# RX_Sheet1.net
KiCad netlist of a schematic drawn in Altium Designer
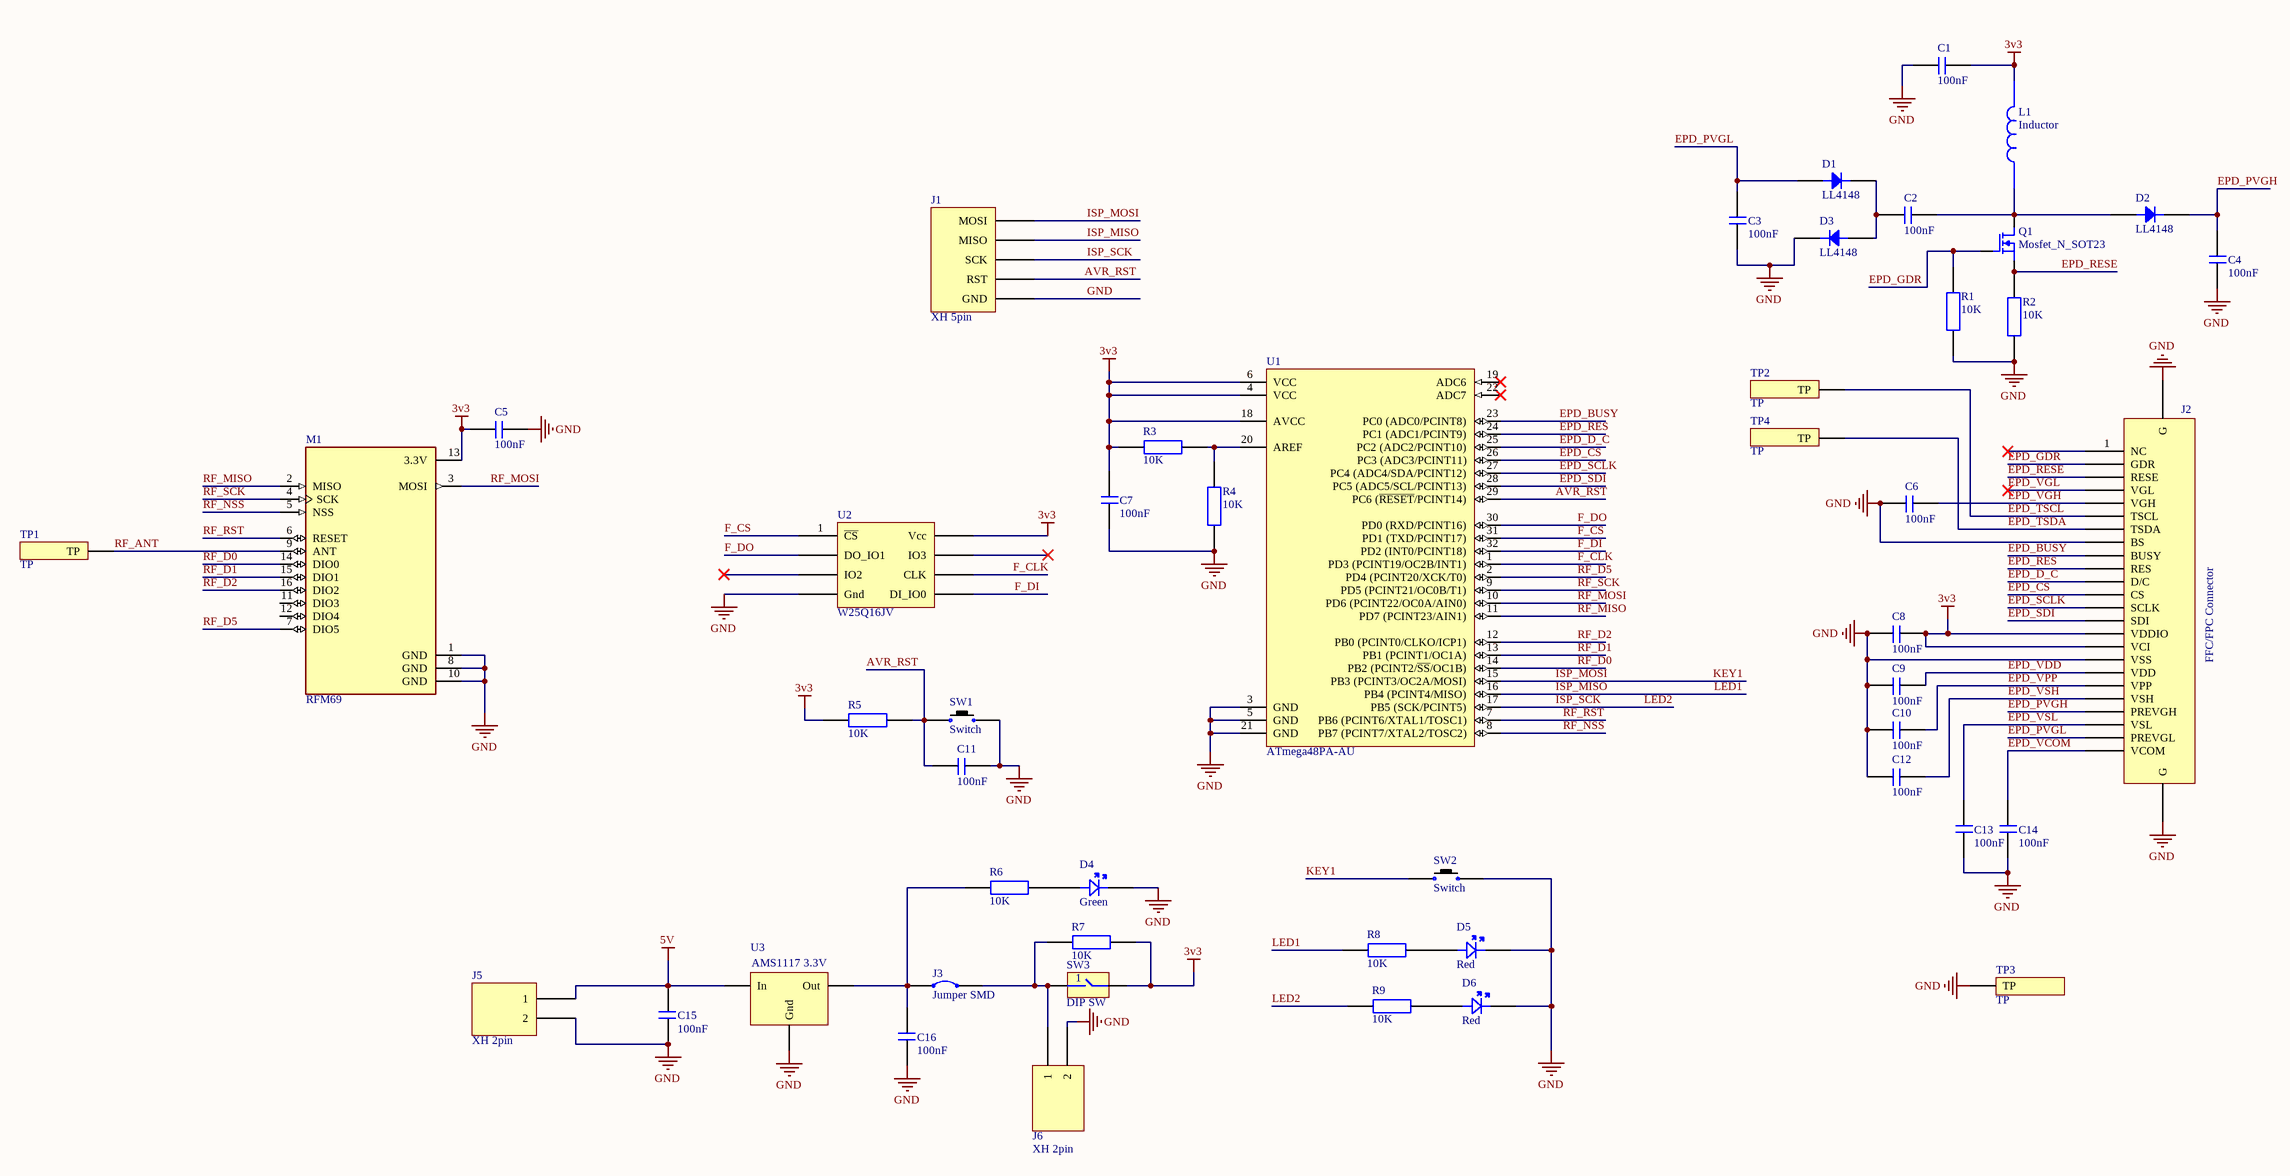
[diagram p0: RX_Sheet1.SchDoc]

(export (version "E")
  (design (tool "Eeschema 10.0.6"))
  (components
    (comp (ref "C1")
      (value "100nF")
      (footprint "CAP_0805")
      (description "Capacitor SMD 0805")
      (libsource (lib "My_Integrated_Library") (part "Cap0805"))
    )
    (comp (ref "C2")
      (value "100nF")
      (footprint "CAP_0805")
      (description "Capacitor SMD 0805")
      (libsource (lib "My_Integrated_Library") (part "Cap0805"))
    )
    (comp (ref "C3")
      (value "100nF")
      (footprint "CAP_0805")
      (description "Capacitor SMD 0805")
      (libsource (lib "My_Integrated_Library") (part "Cap0805"))
    )
    (comp (ref "C4")
      (value "100nF")
      (footprint "CAP_0805")
      (description "Capacitor SMD 0805")
      (libsource (lib "My_Integrated_Library") (part "Cap0805"))
    )
    (comp (ref "C5")
      (value "100nF")
      (footprint "CAP_0805")
      (description "Capacitor SMD 0805")
      (libsource (lib "My_Integrated_Library") (part "Cap0805"))
    )
    (comp (ref "C6")
      (value "100nF")
      (footprint "CAP_0805")
      (description "Capacitor SMD 0805")
      (libsource (lib "My_Integrated_Library") (part "Cap0805"))
    )
    (comp (ref "C7")
      (value "100nF")
      (footprint "CAP_0805")
      (description "Capacitor SMD 0805")
      (libsource (lib "My_Integrated_Library") (part "Cap0805"))
    )
    (comp (ref "C8")
      (value "100nF")
      (footprint "CAP_0805")
      (description "Capacitor SMD 0805")
      (libsource (lib "My_Integrated_Library") (part "Cap0805"))
    )
    (comp (ref "C9")
      (value "100nF")
      (footprint "CAP_0805")
      (description "Capacitor SMD 0805")
      (libsource (lib "My_Integrated_Library") (part "Cap0805"))
    )
    (comp (ref "C10")
      (value "100nF")
      (footprint "CAP_0805")
      (description "Capacitor SMD 0805")
      (libsource (lib "My_Integrated_Library") (part "Cap0805"))
    )
    (comp (ref "C11")
      (value "100nF")
      (footprint "CAP_0805")
      (description "Capacitor SMD 0805")
      (libsource (lib "My_Integrated_Library") (part "Cap0805"))
    )
    (comp (ref "C12")
      (value "100nF")
      (footprint "CAP_0805")
      (description "Capacitor SMD 0805")
      (libsource (lib "My_Integrated_Library") (part "Cap0805"))
    )
    (comp (ref "C13")
      (value "100nF")
      (footprint "CAP_0805")
      (description "Capacitor SMD 0805")
      (libsource (lib "My_Integrated_Library") (part "Cap0805"))
    )
    (comp (ref "C14")
      (value "100nF")
      (footprint "CAP_0805")
      (description "Capacitor SMD 0805")
      (libsource (lib "My_Integrated_Library") (part "Cap0805"))
    )
    (comp (ref "C15")
      (value "100nF")
      (footprint "CAP_0805")
      (description "Capacitor SMD 0805")
      (libsource (lib "My_Integrated_Library") (part "Cap0805"))
    )
    (comp (ref "C16")
      (value "100nF")
      (footprint "CAP_0805")
      (description "Capacitor SMD 0805")
      (libsource (lib "My_Integrated_Library") (part "Cap0805"))
    )
    (comp (ref "D1")
      (value "LL4148")
      (footprint "LL4148")
      (description "Diode SMD LL4148 1206")
      (libsource (lib "My_Integrated_Library") (part "Diode_LL4148"))
    )
    (comp (ref "D2")
      (value "LL4148")
      (footprint "LL4148")
      (description "Diode SMD LL4148 1206")
      (libsource (lib "My_Integrated_Library") (part "Diode_LL4148"))
    )
    (comp (ref "D3")
      (value "LL4148")
      (footprint "LL4148")
      (description "Diode SMD LL4148 1206")
      (libsource (lib "My_Integrated_Library") (part "Diode_LL4148"))
    )
    (comp (ref "D4")
      (value "Green")
      (footprint "LED_0805_Green")
      (description "LED SMD 0805 Green")
      (libsource (lib "My_Integrated_Library") (part "LED_0805_Green"))
    )
    (comp (ref "D5")
      (value "Red")
      (footprint "LED_0805_Red")
      (description "LED SMD 0805 Red")
      (libsource (lib "My_Integrated_Library") (part "LED_0805_Red"))
    )
    (comp (ref "D6")
      (value "Red")
      (footprint "LED_0805_Red")
      (description "LED SMD 0805 Red")
      (libsource (lib "My_Integrated_Library") (part "LED_0805_Red"))
    )
    (comp (ref "J1")
      (value "XH 5pin")
      (footprint "XH-5pin")
      (description "Connector XH Female 5-pin")
      (libsource (lib "My_Integrated_Library") (part "Con_XH_5pin"))
    )
    (comp (ref "J2")
      (value "FFC/FPC Connector")
      (footprint "EPD_CON_24")
      (libsource (lib "My_Integrated_Library") (part "EPD_con_24pin"))
    )
    (comp (ref "J3")
      (value "Jumper SMD")
      (footprint "Jumper_smd")
      (libsource (lib "My_Integrated_Library") (part "Jump_smd"))
    )
    (comp (ref "J5")
      (value "XH 2pin")
      (footprint "XH-2pin")
      (description "Connector XH Female 2-pin")
      (libsource (lib "My_Integrated_Library") (part "Con_XH_2pin"))
    )
    (comp (ref "J6")
      (value "XH 2pin")
      (footprint "XH-2pin")
      (description "Connector XH Female 2-pin")
      (libsource (lib "") (part "Con_XH_2pin_1"))
    )
    (comp (ref "L1")
      (value "Inductor")
      (footprint "L_5x5")
      (description "SMD Power Inductor 10X10mm")
      (libsource (lib "My_Integrated_Library") (part "Inductor_5x5"))
    )
    (comp (ref "M1")
      (value "RFM69")
      (footprint "RFM95W")
      (description "General ISM < 1GHz LoRaâ„¢ Transceiver Module 915MHz Surface Mount")
      (fields (field (name "MP") "RFM95W-915S2") (field (name "MF") "RF Solutions"))
      (libsource (lib "My_Integrated_Library") (part "RFM95W-915S2"))
    )
    (comp (ref "Q1")
      (value "Mosfet_N_SOT23")
      (footprint "SOT23 - N-Channel - duplicate")
      (description "MOSFET N-Channel SMD SOT23")
      (libsource (lib "My_Integrated_Library") (part "Mosfet_N_SOT23"))
    )
    (comp (ref "R1")
      (value "10K")
      (footprint "RES_0805")
      (description "Resistor SMD 0805")
      (libsource (lib "My_Integrated_Library") (part "Res0805"))
    )
    (comp (ref "R2")
      (value "10K")
      (footprint "RES_0805")
      (description "Resistor SMD 0805")
      (libsource (lib "My_Integrated_Library") (part "Res0805"))
    )
    (comp (ref "R3")
      (value "10K")
      (footprint "RES_0805")
      (description "Resistor SMD 0805")
      (libsource (lib "My_Integrated_Library") (part "Res0805"))
    )
    (comp (ref "R4")
      (value "10K")
      (footprint "RES_0805")
      (description "Resistor SMD 0805")
      (libsource (lib "My_Integrated_Library") (part "Res0805"))
    )
    (comp (ref "R5")
      (value "10K")
      (footprint "RES_0805")
      (description "Resistor SMD 0805")
      (libsource (lib "My_Integrated_Library") (part "Res0805"))
    )
    (comp (ref "R6")
      (value "10K")
      (footprint "RES_0805")
      (description "Resistor SMD 0805")
      (libsource (lib "My_Integrated_Library") (part "Res0805"))
    )
    (comp (ref "R7")
      (value "10K")
      (footprint "RES_0805")
      (description "Resistor SMD 0805")
      (libsource (lib "My_Integrated_Library") (part "Res0805"))
    )
    (comp (ref "R8")
      (value "10K")
      (footprint "RES_0805")
      (description "Resistor SMD 0805")
      (libsource (lib "My_Integrated_Library") (part "Res0805"))
    )
    (comp (ref "R9")
      (value "10K")
      (footprint "RES_0805")
      (description "Resistor SMD 0805")
      (libsource (lib "My_Integrated_Library") (part "Res0805"))
    )
    (comp (ref "SW1")
      (value "Switch")
      (footprint "Tact_SW_SMD")
      (description "Tact switch SMD 2pin")
      (libsource (lib "My_Integrated_Library") (part "Tact_sw"))
    )
    (comp (ref "SW2")
      (value "Switch")
      (footprint "Tact_SW_SMD")
      (description "Tact switch SMD 2pin")
      (libsource (lib "My_Integrated_Library") (part "Tact_sw"))
    )
    (comp (ref "SW3")
      (value "DIP SW")
      (footprint "DIP_SW_1key")
      (description "DIP Swtich 1 key")
      (libsource (lib "My_Integrated_Library") (part "DIP_SW_1"))
    )
    (comp (ref "TP1")
      (value "TP")
      (footprint "TP")
      (description "Test point")
      (libsource (lib "") (part "TP_1"))
    )
    (comp (ref "TP2")
      (value "TP")
      (footprint "TP")
      (description "Test point")
      (libsource (lib "") (part "TP_1"))
    )
    (comp (ref "TP3")
      (value "TP")
      (footprint "TP")
      (description "Test point")
      (libsource (lib "My_Integrated_Library") (part "TP"))
    )
    (comp (ref "TP4")
      (value "TP")
      (footprint "TP")
      (description "Test point")
      (libsource (lib "") (part "TP_1"))
    )
    (comp (ref "U1")
      (value "ATmega48PA-AU")
      (footprint "32A_M")
      (fields (field (name "PUBLISHER") "Altium Limited"))
      (libsource (lib "My_Integrated_Library") (part "ATmega48PA-AU"))
    )
    (comp (ref "U2")
      (value "W25Q16JV")
      (footprint "W25Q64")
      (description "Serial Flash Memory 64Mbit")
      (libsource (lib "My_Integrated_Library") (part "W25Q64JV"))
    )
    (comp (ref "U3")
      (value "AMS1117 3.3V")
      (footprint "AMS1117-SOT223")
      (description "AMS1117 Regulator 3.3V SMD SOT223")
      (libsource (lib "My_Integrated_Library") (part "AMS1117-SOT223"))
    )
  )
  (nets
    (net (code "1") (name "/AVR_RST") (class "Default")
      (node (ref "C11") (pin "1") (pinfunction "1_1") (pintype "passive"))
      (node (ref "J1") (pin "4") (pinfunction "RST_4") (pintype "passive"))
      (node (ref "R5") (pin "2") (pinfunction "2_2") (pintype "passive"))
      (node (ref "SW1") (pin "2") (pinfunction "2_2") (pintype "passive"))
      (node (ref "U1") (pin "29") (pinfunction "PC6_(~{RESET}/PCINT14)_29") (pintype "bidirectional"))
    )
    (net (code "2") (name "/EPD_BUSY") (class "Default")
      (node (ref "J2") (pin "9") (pinfunction "BUSY_9") (pintype "passive"))
      (node (ref "U1") (pin "23") (pinfunction "PC0_(ADC0/PCINT8)_23") (pintype "bidirectional"))
    )
    (net (code "3") (name "/EPD_CS") (class "Default")
      (node (ref "J2") (pin "12") (pinfunction "CS_12") (pintype "passive"))
      (node (ref "U1") (pin "26") (pinfunction "PC3_(ADC3/PCINT11)_26") (pintype "bidirectional"))
    )
    (net (code "4") (name "/EPD_D_C") (class "Default")
      (node (ref "J2") (pin "11") (pinfunction "D/C_11") (pintype "passive"))
      (node (ref "U1") (pin "25") (pinfunction "PC2_(ADC2/PCINT10)_25") (pintype "bidirectional"))
    )
    (net (code "5") (name "/EPD_GDR") (class "Default")
      (node (ref "J2") (pin "2") (pinfunction "GDR_2") (pintype "passive"))
      (node (ref "Q1") (pin "G") (pinfunction "G_G") (pintype "passive"))
      (node (ref "R1") (pin "2") (pinfunction "2_2") (pintype "passive"))
    )
    (net (code "6") (name "/EPD_PVGH") (class "Default")
      (node (ref "C4") (pin "2") (pinfunction "2_2") (pintype "passive"))
      (node (ref "D2") (pin "K") (pinfunction "K_K") (pintype "passive"))
      (node (ref "J2") (pin "21") (pinfunction "PREVGH_21") (pintype "passive"))
    )
    (net (code "7") (name "/EPD_PVGL") (class "Default")
      (node (ref "C3") (pin "2") (pinfunction "2_2") (pintype "passive"))
      (node (ref "D1") (pin "A") (pinfunction "A_A") (pintype "passive"))
      (node (ref "J2") (pin "23") (pinfunction "PREVGL_23") (pintype "passive"))
    )
    (net (code "8") (name "/EPD_RES") (class "Default")
      (node (ref "J2") (pin "10") (pinfunction "RES_10") (pintype "passive"))
      (node (ref "U1") (pin "24") (pinfunction "PC1_(ADC1/PCINT9)_24") (pintype "bidirectional"))
    )
    (net (code "9") (name "/EPD_RESE") (class "Default")
      (node (ref "J2") (pin "3") (pinfunction "RESE_3") (pintype "passive"))
      (node (ref "Q1") (pin "S") (pinfunction "S_S") (pintype "passive"))
      (node (ref "R2") (pin "2") (pinfunction "2_2") (pintype "passive"))
    )
    (net (code "10") (name "/EPD_SCLK") (class "Default")
      (node (ref "J2") (pin "13") (pinfunction "SCLK_13") (pintype "passive"))
      (node (ref "U1") (pin "27") (pinfunction "PC4_(ADC4/SDA/PCINT12)_27") (pintype "bidirectional"))
    )
    (net (code "11") (name "/EPD_SDI") (class "Default")
      (node (ref "J2") (pin "14") (pinfunction "SDI_14") (pintype "passive"))
      (node (ref "U1") (pin "28") (pinfunction "PC5_(ADC5/SCL/PCINT13)_28") (pintype "bidirectional"))
    )
    (net (code "12") (name "/EPD_TSCL") (class "Default")
      (node (ref "J2") (pin "6") (pinfunction "TSCL_6") (pintype "passive"))
      (node (ref "TP2") (pin "1") (pinfunction "TP_1") (pintype "passive"))
    )
    (net (code "13") (name "/EPD_TSDA") (class "Default")
      (node (ref "J2") (pin "7") (pinfunction "TSDA_7") (pintype "passive"))
      (node (ref "TP4") (pin "1") (pinfunction "TP_1") (pintype "passive"))
    )
    (net (code "14") (name "/EPD_VCOM") (class "Default")
      (node (ref "C14") (pin "2") (pinfunction "2_2") (pintype "passive"))
      (node (ref "J2") (pin "24") (pinfunction "VCOM_24") (pintype "passive"))
    )
    (net (code "15") (name "/EPD_VDD") (class "Default")
      (node (ref "C9") (pin "2") (pinfunction "2_2") (pintype "passive"))
      (node (ref "J2") (pin "18") (pinfunction "VDD_18") (pintype "passive"))
    )
    (net (code "16") (name "/EPD_VGH") (class "Default")
      (node (ref "C6") (pin "2") (pinfunction "2_2") (pintype "passive"))
      (node (ref "J2") (pin "5") (pinfunction "VGH_5") (pintype "passive"))
    )
    (net (code "17") (name "/EPD_VGL") (class "Default")
      (node (ref "J2") (pin "4") (pinfunction "VGL_4") (pintype "passive+no_connect"))
    )
    (net (code "18") (name "/EPD_VPP") (class "Default")
      (node (ref "C10") (pin "2") (pinfunction "2_2") (pintype "passive"))
      (node (ref "J2") (pin "19") (pinfunction "VPP_19") (pintype "passive"))
    )
    (net (code "19") (name "/EPD_VSH") (class "Default")
      (node (ref "C12") (pin "2") (pinfunction "2_2") (pintype "passive"))
      (node (ref "J2") (pin "20") (pinfunction "VSH_20") (pintype "passive"))
    )
    (net (code "20") (name "/EPD_VSL") (class "Default")
      (node (ref "C13") (pin "2") (pinfunction "2_2") (pintype "passive"))
      (node (ref "J2") (pin "22") (pinfunction "VSL_22") (pintype "passive"))
    )
    (net (code "21") (name "/F_CLK") (class "Default")
      (node (ref "U1") (pin "1") (pinfunction "PD3_(PCINT19/OC2B/INT1)_1") (pintype "bidirectional"))
      (node (ref "U2") (pin "6") (pinfunction "CLK_6") (pintype "passive"))
    )
    (net (code "22") (name "/F_CS") (class "Default")
      (node (ref "U1") (pin "31") (pinfunction "PD1_(TXD/PCINT17)_31") (pintype "bidirectional"))
      (node (ref "U2") (pin "1") (pinfunction "~{CS}_1") (pintype "passive"))
    )
    (net (code "23") (name "/F_DI") (class "Default")
      (node (ref "U1") (pin "32") (pinfunction "PD2_(INT0/PCINT18)_32") (pintype "bidirectional"))
      (node (ref "U2") (pin "5") (pinfunction "DI_IO0_5") (pintype "passive"))
    )
    (net (code "24") (name "/F_DO") (class "Default")
      (node (ref "U1") (pin "30") (pinfunction "PD0_(RXD/PCINT16)_30") (pintype "bidirectional"))
      (node (ref "U2") (pin "2") (pinfunction "DO_IO1_2") (pintype "passive"))
    )
    (net (code "25") (name "/ISP_MISO") (class "Default")
      (node (ref "J1") (pin "2") (pinfunction "MISO_2") (pintype "passive"))
      (node (ref "R8") (pin "1") (pinfunction "1_1") (pintype "passive"))
      (node (ref "U1") (pin "16") (pinfunction "PB4_(PCINT4/MISO)_16") (pintype "bidirectional"))
    )
    (net (code "26") (name "/ISP_MOSI") (class "Default")
      (node (ref "J1") (pin "1") (pinfunction "MOSI_1") (pintype "passive"))
      (node (ref "SW2") (pin "2") (pinfunction "2_2") (pintype "passive"))
      (node (ref "U1") (pin "15") (pinfunction "PB3_(PCINT3/OC2A/MOSI)_15") (pintype "bidirectional"))
    )
    (net (code "27") (name "/ISP_SCK") (class "Default")
      (node (ref "J1") (pin "3") (pinfunction "SCK_3") (pintype "passive"))
      (node (ref "R9") (pin "1") (pinfunction "1_1") (pintype "passive"))
      (node (ref "U1") (pin "17") (pinfunction "PB5_(SCK/PCINT5)_17") (pintype "bidirectional"))
    )
    (net (code "28") (name "/RF_ANT") (class "Default")
      (node (ref "M1") (pin "9") (pinfunction "ANT_9") (pintype "bidirectional"))
      (node (ref "TP1") (pin "1") (pinfunction "TP_1") (pintype "passive"))
    )
    (net (code "29") (name "/RF_D0") (class "Default")
      (node (ref "M1") (pin "14") (pinfunction "DIO0_14") (pintype "bidirectional"))
      (node (ref "U1") (pin "14") (pinfunction "PB2_(PCINT2/~{SS}/OC1B)_14") (pintype "bidirectional"))
    )
    (net (code "30") (name "/RF_D1") (class "Default")
      (node (ref "M1") (pin "15") (pinfunction "DIO1_15") (pintype "bidirectional"))
      (node (ref "U1") (pin "13") (pinfunction "PB1_(PCINT1/OC1A)_13") (pintype "bidirectional"))
    )
    (net (code "31") (name "/RF_D2") (class "Default")
      (node (ref "M1") (pin "16") (pinfunction "DIO2_16") (pintype "bidirectional"))
      (node (ref "U1") (pin "12") (pinfunction "PB0_(PCINT0/CLKO/ICP1)_12") (pintype "bidirectional"))
    )
    (net (code "32") (name "/RF_D5") (class "Default")
      (node (ref "M1") (pin "7") (pinfunction "DIO5_7") (pintype "bidirectional"))
      (node (ref "U1") (pin "2") (pinfunction "PD4_(PCINT20/XCK/T0)_2") (pintype "bidirectional"))
    )
    (net (code "33") (name "/RF_MISO") (class "Default")
      (node (ref "M1") (pin "2") (pinfunction "MISO_2") (pintype "input"))
      (node (ref "U1") (pin "11") (pinfunction "PD7_(PCINT23/AIN1)_11") (pintype "bidirectional"))
    )
    (net (code "34") (name "/RF_MOSI") (class "Default")
      (node (ref "M1") (pin "3") (pinfunction "MOSI_3") (pintype "output"))
      (node (ref "U1") (pin "10") (pinfunction "PD6_(PCINT22/OC0A/AIN0)_10") (pintype "bidirectional"))
    )
    (net (code "35") (name "/RF_NSS") (class "Default")
      (node (ref "M1") (pin "5") (pinfunction "NSS_5") (pintype "input"))
      (node (ref "U1") (pin "8") (pinfunction "PB7_(PCINT7/XTAL2/TOSC2)_8") (pintype "bidirectional"))
    )
    (net (code "36") (name "/RF_RST") (class "Default")
      (node (ref "M1") (pin "6") (pinfunction "RESET_6") (pintype "bidirectional"))
      (node (ref "U1") (pin "7") (pinfunction "PB6_(PCINT6/XTAL1/TOSC1)_7") (pintype "bidirectional"))
    )
    (net (code "37") (name "/RF_SCK") (class "Default")
      (node (ref "M1") (pin "4") (pinfunction "SCK_4") (pintype "input"))
      (node (ref "U1") (pin "9") (pinfunction "PD5_(PCINT21/OC0B/T1)_9") (pintype "bidirectional"))
    )
    (net (code "38") (name "3v3") (class "Default")
      (node (ref "C1") (pin "2") (pinfunction "2_2") (pintype "passive"))
      (node (ref "C5") (pin "1") (pinfunction "1_1") (pintype "passive"))
      (node (ref "C7") (pin "2") (pinfunction "2_2") (pintype "passive"))
      (node (ref "C8") (pin "2") (pinfunction "2_2") (pintype "passive"))
      (node (ref "J2") (pin "15") (pinfunction "VDDIO_15") (pintype "passive"))
      (node (ref "J2") (pin "16") (pinfunction "VCI_16") (pintype "passive"))
      (node (ref "L1") (pin "2") (pinfunction "2_2") (pintype "passive"))
      (node (ref "M1") (pin "13") (pinfunction "3.3V_13") (pintype "power_in"))
      (node (ref "R3") (pin "1") (pinfunction "1_1") (pintype "passive"))
      (node (ref "R5") (pin "1") (pinfunction "1_1") (pintype "passive"))
      (node (ref "R7") (pin "2") (pinfunction "2_2") (pintype "passive"))
      (node (ref "SW3") (pin "2") (pinfunction "2_2") (pintype "passive"))
      (node (ref "U1") (pin "18") (pinfunction "AVCC_18") (pintype "power_in"))
      (node (ref "U1") (pin "4") (pinfunction "VCC_4") (pintype "power_in"))
      (node (ref "U1") (pin "6") (pinfunction "VCC_6") (pintype "power_in"))
      (node (ref "U2") (pin "8") (pinfunction "Vcc_8") (pintype "passive"))
    )
    (net (code "39") (name "5V") (class "Default")
      (node (ref "C15") (pin "1") (pinfunction "1_1") (pintype "passive"))
      (node (ref "J5") (pin "1") (pinfunction "1_1") (pintype "passive"))
      (node (ref "U3") (pin "1") (pinfunction "In_1") (pintype "passive"))
    )
    (net (code "40") (name "GND") (class "Default")
      (node (ref "C1") (pin "1") (pinfunction "1_1") (pintype "passive"))
      (node (ref "C10") (pin "1") (pinfunction "1_1") (pintype "passive"))
      (node (ref "C11") (pin "2") (pinfunction "2_2") (pintype "passive"))
      (node (ref "C12") (pin "1") (pinfunction "1_1") (pintype "passive"))
      (node (ref "C13") (pin "1") (pinfunction "1_1") (pintype "passive"))
      (node (ref "C14") (pin "1") (pinfunction "1_1") (pintype "passive"))
      (node (ref "C15") (pin "2") (pinfunction "2_2") (pintype "passive"))
      (node (ref "C16") (pin "2") (pinfunction "2_2") (pintype "passive"))
      (node (ref "C3") (pin "1") (pinfunction "1_1") (pintype "passive"))
      (node (ref "C4") (pin "1") (pinfunction "1_1") (pintype "passive"))
      (node (ref "C5") (pin "2") (pinfunction "2_2") (pintype "passive"))
      (node (ref "C6") (pin "1") (pinfunction "1_1") (pintype "passive"))
      (node (ref "C7") (pin "1") (pinfunction "1_1") (pintype "passive"))
      (node (ref "C8") (pin "1") (pinfunction "1_1") (pintype "passive"))
      (node (ref "C9") (pin "1") (pinfunction "1_1") (pintype "passive"))
      (node (ref "D3") (pin "K") (pinfunction "K_K") (pintype "passive"))
      (node (ref "D4") (pin "2") (pinfunction "2_2") (pintype "passive"))
      (node (ref "D5") (pin "2") (pinfunction "2_2") (pintype "passive"))
      (node (ref "D6") (pin "2") (pinfunction "2_2") (pintype "passive"))
      (node (ref "J1") (pin "5") (pinfunction "GND_5") (pintype "passive"))
      (node (ref "J2") (pin "17") (pinfunction "VSS_17") (pintype "passive"))
      (node (ref "J2") (pin "25") (pinfunction "G_25") (pintype "passive"))
      (node (ref "J2") (pin "26") (pinfunction "G_26") (pintype "passive"))
      (node (ref "J2") (pin "8") (pinfunction "BS_8") (pintype "passive"))
      (node (ref "J5") (pin "2") (pinfunction "2_2") (pintype "passive"))
      (node (ref "J6") (pin "2") (pinfunction "2_2") (pintype "passive"))
      (node (ref "M1") (pin "1") (pinfunction "GND_1") (pintype "power_in"))
      (node (ref "M1") (pin "10") (pinfunction "GND_10") (pintype "power_in"))
      (node (ref "M1") (pin "8") (pinfunction "GND_8") (pintype "power_in"))
      (node (ref "R1") (pin "1") (pinfunction "1_1") (pintype "passive"))
      (node (ref "R2") (pin "1") (pinfunction "1_1") (pintype "passive"))
      (node (ref "R4") (pin "1") (pinfunction "1_1") (pintype "passive"))
      (node (ref "SW1") (pin "1") (pinfunction "1_1") (pintype "passive"))
      (node (ref "SW2") (pin "1") (pinfunction "1_1") (pintype "passive"))
      (node (ref "TP3") (pin "1") (pinfunction "TP_1") (pintype "passive"))
      (node (ref "U1") (pin "21") (pinfunction "GND_21") (pintype "power_in"))
      (node (ref "U1") (pin "3") (pinfunction "GND_3") (pintype "power_in"))
      (node (ref "U1") (pin "5") (pinfunction "GND_5") (pintype "power_in"))
      (node (ref "U2") (pin "4") (pinfunction "Gnd_4") (pintype "passive"))
      (node (ref "U3") (pin "2") (pinfunction "Gnd_2") (pintype "passive"))
    )
    (net (code "41") (name "Net-(C2-Pad1)") (class "Default")
      (node (ref "C2") (pin "1") (pinfunction "1_1") (pintype "passive"))
      (node (ref "D1") (pin "K") (pinfunction "K_K") (pintype "passive"))
      (node (ref "D3") (pin "A") (pinfunction "A_A") (pintype "passive"))
    )
    (net (code "42") (name "Net-(C2-Pad2)") (class "Default")
      (node (ref "C2") (pin "2") (pinfunction "2_2") (pintype "passive"))
      (node (ref "D2") (pin "A") (pinfunction "A_A") (pintype "passive"))
      (node (ref "L1") (pin "1") (pinfunction "1_1") (pintype "passive"))
      (node (ref "Q1") (pin "D") (pinfunction "D_D") (pintype "passive"))
    )
    (net (code "43") (name "Net-(D4-Pad1)") (class "Default")
      (node (ref "D4") (pin "1") (pinfunction "1_1") (pintype "passive"))
      (node (ref "R6") (pin "2") (pinfunction "2_2") (pintype "passive"))
    )
    (net (code "44") (name "Net-(D5-Pad1)") (class "Default")
      (node (ref "D5") (pin "1") (pinfunction "1_1") (pintype "passive"))
      (node (ref "R8") (pin "2") (pinfunction "2_2") (pintype "passive"))
    )
    (net (code "45") (name "Net-(D6-Pad1)") (class "Default")
      (node (ref "D6") (pin "1") (pinfunction "1_1") (pintype "passive"))
      (node (ref "R9") (pin "2") (pinfunction "2_2") (pintype "passive"))
    )
    (net (code "46") (name "Net-(J3-Pad1)") (class "Default")
      (node (ref "J3") (pin "1") (pinfunction "1_1") (pintype "passive"))
      (node (ref "J6") (pin "1") (pinfunction "1_1") (pintype "passive"))
      (node (ref "R7") (pin "1") (pinfunction "1_1") (pintype "passive"))
      (node (ref "SW3") (pin "1") (pinfunction "1_1") (pintype "passive"))
    )
    (net (code "47") (name "Net-(U1-AREF)") (class "Default")
      (node (ref "R3") (pin "2") (pinfunction "2_2") (pintype "passive"))
      (node (ref "R4") (pin "2") (pinfunction "2_2") (pintype "passive"))
      (node (ref "U1") (pin "20") (pinfunction "AREF_20") (pintype "passive"))
    )
    (net (code "48") (name "Net-(U3-Out)") (class "Default")
      (node (ref "C16") (pin "1") (pinfunction "1_1") (pintype "passive"))
      (node (ref "J3") (pin "2") (pinfunction "2_2") (pintype "passive"))
      (node (ref "R6") (pin "1") (pinfunction "1_1") (pintype "passive"))
      (node (ref "U3") (pin "3") (pinfunction "Out_3") (pintype "passive"))
    )
    (net (code "49") (name "unconnected-(J2-NC-Pad1)") (class "Default")
      (node (ref "J2") (pin "1") (pinfunction "NC_1") (pintype "passive+no_connect"))
    )
    (net (code "50") (name "unconnected-(M1-DIO3-Pad11)") (class "Default")
      (node (ref "M1") (pin "11") (pinfunction "DIO3_11") (pintype "bidirectional"))
    )
    (net (code "51") (name "unconnected-(M1-DIO4-Pad12)") (class "Default")
      (node (ref "M1") (pin "12") (pinfunction "DIO4_12") (pintype "bidirectional"))
    )
    (net (code "52") (name "unconnected-(U1-ADC6-Pad19)") (class "Default")
      (node (ref "U1") (pin "19") (pinfunction "ADC6_19") (pintype "input+no_connect"))
    )
    (net (code "53") (name "unconnected-(U1-ADC7-Pad22)") (class "Default")
      (node (ref "U1") (pin "22") (pinfunction "ADC7_22") (pintype "input+no_connect"))
    )
    (net (code "54") (name "unconnected-(U2-IO2-Pad3)") (class "Default")
      (node (ref "U2") (pin "3") (pinfunction "IO2_3") (pintype "passive+no_connect"))
    )
    (net (code "55") (name "unconnected-(U2-IO3-Pad7)") (class "Default")
      (node (ref "U2") (pin "7") (pinfunction "IO3_7") (pintype "passive+no_connect"))
    )
  )
)
